# ethernet.net
KiCad netlist of a schematic drawn in Altium Designer
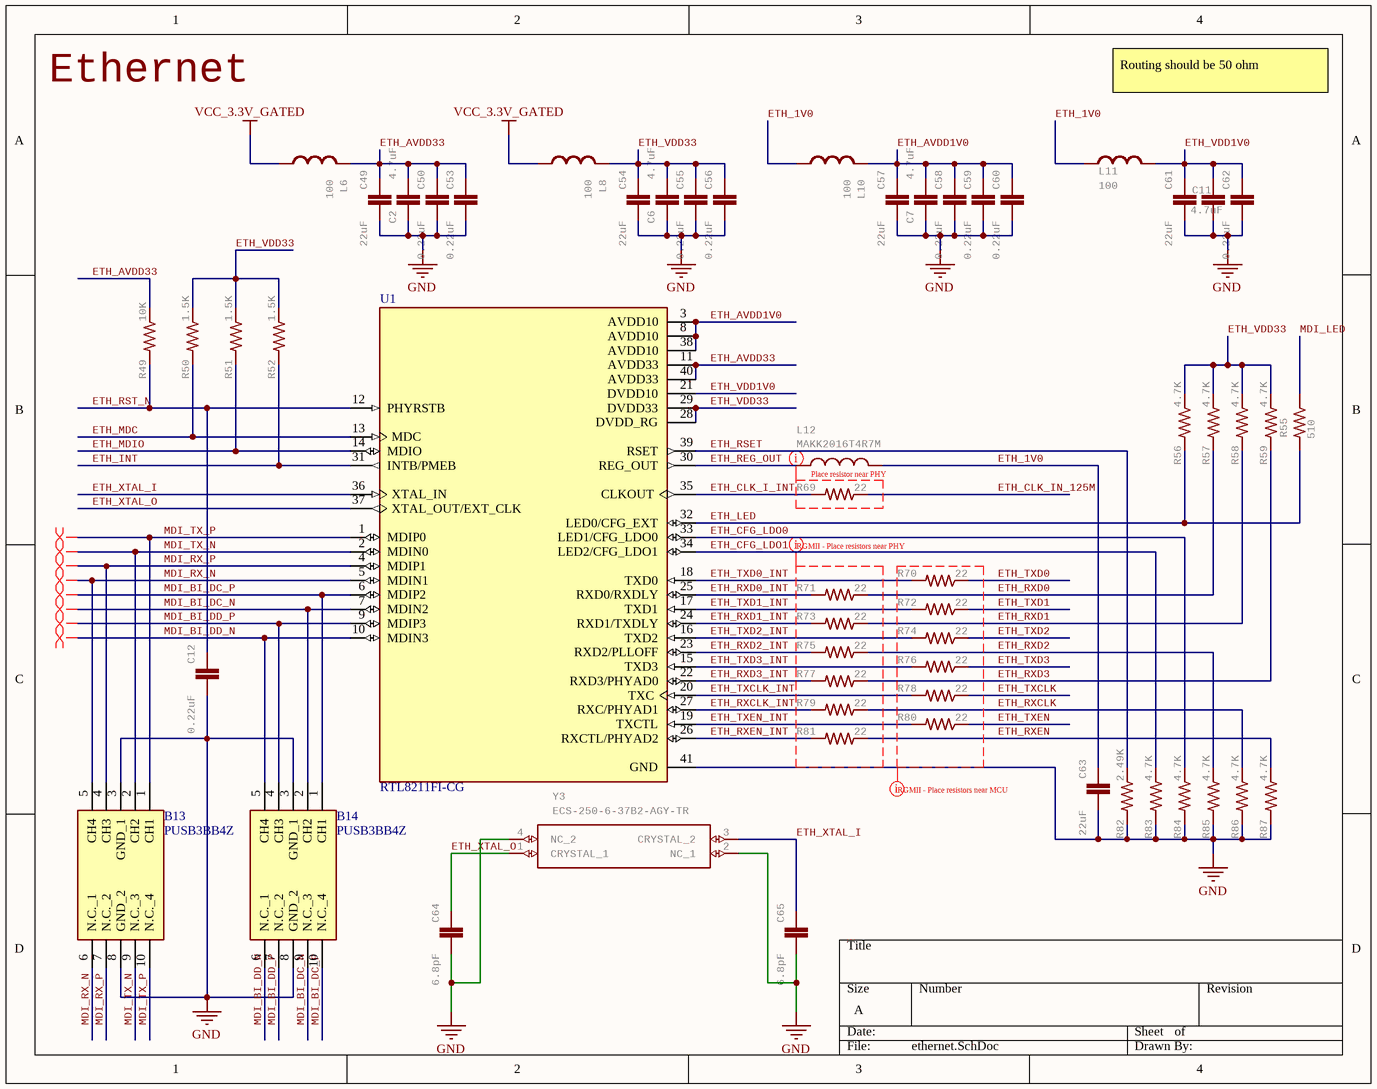
[diagram p0: ethernet.SchDoc]

(export (version "E")
  (design (tool "Eeschema 10.0.6"))
  (components
    (comp (ref "B13")
      (value "PUSB3BB4Z")
      (footprint "SON50P100X250X50-10N")
      (description "PUSB3BB4 - Extremely low capacitance bidirectional ESD protection diode array@en-us")
      (fields (field (name "MOUSER PART NUMBER") "771-PUSB3BB4Z"))
      (libsource (lib "PUSB3BB4Z") (part "PUSB3BB4Z"))
    )
    (comp (ref "B14")
      (value "PUSB3BB4Z")
      (footprint "SON50P100X250X50-10N")
      (description "PUSB3BB4 - Extremely low capacitance bidirectional ESD protection diode array@en-us")
      (fields (field (name "MOUSER PART NUMBER") "771-PUSB3BB4Z"))
      (libsource (lib "PUSB3BB4Z") (part "PUSB3BB4Z"))
    )
    (comp (ref "C2")
      (value "4.7uF")
      (footprint "0402-CAP")
      (description "CapacitorStandard 0603 ceramic capacitor, and 0.1\" leaded capacitor.")
      (fields (field (name "MPN") "JMK105BBJ475MV-F"))
      (libsource (lib "rt10") (part "CAP0402-CAP"))
    )
    (comp (ref "C6")
      (value "4.7uF")
      (footprint "0402-CAP")
      (description "CapacitorStandard 0603 ceramic capacitor, and 0.1\" leaded capacitor.")
      (fields (field (name "MPN") "JMK105BBJ475MV-F"))
      (libsource (lib "rt10") (part "CAP0402-CAP"))
    )
    (comp (ref "C7")
      (value "4.7uF")
      (footprint "0402-CAP")
      (description "CapacitorStandard 0603 ceramic capacitor, and 0.1\" leaded capacitor.")
      (fields (field (name "MPN") "JMK105BBJ475MV-F"))
      (libsource (lib "rt10") (part "CAP0402-CAP"))
    )
    (comp (ref "C11")
      (value "4.7uF")
      (footprint "0402-CAP")
      (description "CapacitorStandard 0603 ceramic capacitor, and 0.1\" leaded capacitor.")
      (fields (field (name "MPN") "JMK105BBJ475MV-F"))
      (libsource (lib "rt10") (part "CAP0402-CAP"))
    )
    (comp (ref "C12")
      (value "0.22uF")
      (footprint "C0201")
      (description "CAPACITOR, European symbol")
      (fields (field (name "MPN") "GRM033R60J224ME15D"))
      (libsource (lib "rt10") (part "C-EUC0201"))
    )
    (comp (ref "C49")
      (value "22uF")
      (footprint "0603-CAP")
      (fields (field (name "MPN") "GRM188R60G226MEA0D"))
      (libsource (lib "rt10") (part "22UF-0805-6.3V-20%"))
    )
    (comp (ref "C50")
      (value "0.22uF")
      (footprint "C0201")
      (description "CAPACITOR, European symbol")
      (fields (field (name "MPN") "GRM033R60J224ME15D"))
      (libsource (lib "rt10") (part "C-EUC0201"))
    )
    (comp (ref "C53")
      (value "0.22uF")
      (footprint "C0201")
      (description "CAPACITOR, European symbol")
      (fields (field (name "MPN") "GRM033R60J224ME15D"))
      (libsource (lib "rt10") (part "C-EUC0201"))
    )
    (comp (ref "C54")
      (value "22uF")
      (footprint "0603-CAP")
      (fields (field (name "MPN") "GRM188R60G226MEA0D"))
      (libsource (lib "rt10") (part "22UF-0805-6.3V-20%"))
    )
    (comp (ref "C55")
      (value "0.22uF")
      (footprint "C0201")
      (description "CAPACITOR, European symbol")
      (fields (field (name "MPN") "GRM033R60J224ME15D"))
      (libsource (lib "rt10") (part "C-EUC0201"))
    )
    (comp (ref "C56")
      (value "0.22uF")
      (footprint "C0201")
      (description "CAPACITOR, European symbol")
      (fields (field (name "MPN") "GRM033R60J224ME15D"))
      (libsource (lib "rt10") (part "C-EUC0201"))
    )
    (comp (ref "C57")
      (value "22uF")
      (footprint "0603-CAP")
      (fields (field (name "MPN") "GRM188R60G226MEA0D"))
      (libsource (lib "rt10") (part "22UF-0805-6.3V-20%"))
    )
    (comp (ref "C58")
      (value "0.22uF")
      (footprint "C0201")
      (description "CAPACITOR, European symbol")
      (fields (field (name "MPN") "GRM033R60J224ME15D"))
      (libsource (lib "rt10") (part "C-EUC0201"))
    )
    (comp (ref "C59")
      (value "0.22uF")
      (footprint "C0201")
      (description "CAPACITOR, European symbol")
      (fields (field (name "MPN") "GRM033R60J224ME15D"))
      (libsource (lib "rt10") (part "C-EUC0201"))
    )
    (comp (ref "C60")
      (value "0.22uF")
      (footprint "C0201")
      (description "CAPACITOR, European symbol")
      (fields (field (name "MPN") "GRM033R60J224ME15D"))
      (libsource (lib "rt10") (part "C-EUC0201"))
    )
    (comp (ref "C61")
      (value "22uF")
      (footprint "0603-CAP")
      (fields (field (name "MPN") "GRM188R60G226MEA0D"))
      (libsource (lib "rt10") (part "22UF-0805-6.3V-20%"))
    )
    (comp (ref "C62")
      (value "0.22uF")
      (footprint "C0201")
      (description "CAPACITOR, European symbol")
      (fields (field (name "MPN") "GRM033R60J224ME15D"))
      (libsource (lib "rt10") (part "C-EUC0201"))
    )
    (comp (ref "C63")
      (value "22uF")
      (footprint "0603-CAP")
      (fields (field (name "MPN") "GRM188R60G226MEA0D"))
      (libsource (lib "rt10") (part "22UF-0805-6.3V-20%"))
    )
    (comp (ref "C64")
      (value "6.8pF")
      (footprint "C0201")
      (description "CAPACITOR, European symbol")
      (fields (field (name "MPN") "GRM0335C1H6R8BA01D"))
      (libsource (lib "rt10") (part "C-EUC0201"))
    )
    (comp (ref "C65")
      (value "6.8pF")
      (footprint "C0201")
      (description "CAPACITOR, European symbol")
      (fields (field (name "MPN") "GRM0335C1H6R8BA01D"))
      (libsource (lib "rt10") (part "C-EUC0201"))
    )
    (comp (ref "L6")
      (value "100")
      (footprint "C0402")
      (fields (field (name "MPN") "MFBM1V1005-101-R"))
      (libsource (lib "rt10") (part "INDUCTOR0402"))
    )
    (comp (ref "L8")
      (value "100")
      (footprint "C0402")
      (fields (field (name "MPN") "MFBM1V1005-101-R"))
      (libsource (lib "rt10") (part "INDUCTOR0402"))
    )
    (comp (ref "L10")
      (value "100")
      (footprint "C0402")
      (fields (field (name "MPN") "MFBM1V1005-101-R"))
      (libsource (lib "rt10") (part "INDUCTOR0402"))
    )
    (comp (ref "L11")
      (value "100")
      (footprint "C0402")
      (fields (field (name "MPN") "MFBM1V1005-101-R"))
      (libsource (lib "rt10") (part "INDUCTOR0402"))
    )
    (comp (ref "L12")
      (value "MAKK2016T4R7M")
      (footprint "INDC2016X100N")
      (description "INDUCTOR, METAL CORE Check availability")
      (fields (field (name "MF") "Taiyo Yuden"))
      (libsource (lib "rt10") (part "MAKK2016T2R2M"))
    )
    (comp (ref "R49")
      (value "10K")
      (footprint "R0201")
      (fields (field (name "MPN") "CR0201-JW-103GLF"))
      (libsource (lib "openmv-ae3") (part "RESISTOR0402-RES"))
    )
    (comp (ref "R50")
      (value "1.5K")
      (footprint "R0201")
      (fields (field (name "MPN") "AC0201JR-071K5L"))
      (libsource (lib "openmv-ae3") (part "RESISTOR0402-RES"))
    )
    (comp (ref "R51")
      (value "1.5K")
      (footprint "R0201")
      (fields (field (name "MPN") "AC0201JR-071K5L"))
      (libsource (lib "openmv-ae3") (part "RESISTOR0402-RES"))
    )
    (comp (ref "R52")
      (value "1.5K")
      (footprint "R0201")
      (fields (field (name "MPN") "AC0201JR-071K5L"))
      (libsource (lib "openmv-ae3") (part "RESISTOR0402-RES"))
    )
    (comp (ref "R55")
      (value "510")
      (footprint "0402-RES")
      (description "ResistorBasic schematic elements and footprints for 0603, 1206, and PTH resistors.")
      (fields (field (name "MPN") "RC0402FR-07510RL"))
      (libsource (lib "rt10") (part "RESISTOR0402-RES"))
    )
    (comp (ref "R56")
      (value "4.7K")
      (footprint "R0201")
      (fields (field (name "MPN") "CR0201-FW-4701GLF"))
      (libsource (lib "openmv-ae3") (part "RESISTOR0402-RES"))
    )
    (comp (ref "R57")
      (value "4.7K")
      (footprint "R0201")
      (fields (field (name "MPN") "CR0201-FW-4701GLF"))
      (libsource (lib "openmv-ae3") (part "RESISTOR0402-RES"))
    )
    (comp (ref "R58")
      (value "4.7K")
      (footprint "R0201")
      (fields (field (name "MPN") "CR0201-FW-4701GLF"))
      (libsource (lib "openmv-ae3") (part "RESISTOR0402-RES"))
    )
    (comp (ref "R59")
      (value "4.7K")
      (footprint "R0201")
      (fields (field (name "MPN") "CR0201-FW-4701GLF"))
      (libsource (lib "openmv-ae3") (part "RESISTOR0402-RES"))
    )
    (comp (ref "R69")
      (value "22")
      (footprint "R0201")
      (fields (field (name "MPN") "CR0201-JW-220GLF"))
      (libsource (lib "openmv-ae3") (part "RESISTOR0402-RES"))
    )
    (comp (ref "R70")
      (value "22")
      (footprint "R0201")
      (fields (field (name "MPN") "CR0201-JW-220GLF"))
      (libsource (lib "openmv-ae3") (part "RESISTOR0402-RES"))
    )
    (comp (ref "R71")
      (value "22")
      (footprint "R0201")
      (fields (field (name "MPN") "CR0201-JW-220GLF"))
      (libsource (lib "openmv-ae3") (part "RESISTOR0402-RES"))
    )
    (comp (ref "R72")
      (value "22")
      (footprint "R0201")
      (fields (field (name "MPN") "CR0201-JW-220GLF"))
      (libsource (lib "openmv-ae3") (part "RESISTOR0402-RES"))
    )
    (comp (ref "R73")
      (value "22")
      (footprint "R0201")
      (fields (field (name "MPN") "CR0201-JW-220GLF"))
      (libsource (lib "openmv-ae3") (part "RESISTOR0402-RES"))
    )
    (comp (ref "R74")
      (value "22")
      (footprint "R0201")
      (fields (field (name "MPN") "CR0201-JW-220GLF"))
      (libsource (lib "openmv-ae3") (part "RESISTOR0402-RES"))
    )
    (comp (ref "R75")
      (value "22")
      (footprint "R0201")
      (fields (field (name "MPN") "CR0201-JW-220GLF"))
      (libsource (lib "openmv-ae3") (part "RESISTOR0402-RES"))
    )
    (comp (ref "R76")
      (value "22")
      (footprint "R0201")
      (fields (field (name "MPN") "CR0201-JW-220GLF"))
      (libsource (lib "openmv-ae3") (part "RESISTOR0402-RES"))
    )
    (comp (ref "R77")
      (value "22")
      (footprint "R0201")
      (fields (field (name "MPN") "CR0201-JW-220GLF"))
      (libsource (lib "openmv-ae3") (part "RESISTOR0402-RES"))
    )
    (comp (ref "R78")
      (value "22")
      (footprint "R0201")
      (fields (field (name "MPN") "CR0201-JW-220GLF"))
      (libsource (lib "openmv-ae3") (part "RESISTOR0402-RES"))
    )
    (comp (ref "R79")
      (value "22")
      (footprint "R0201")
      (fields (field (name "MPN") "CR0201-JW-220GLF"))
      (libsource (lib "openmv-ae3") (part "RESISTOR0402-RES"))
    )
    (comp (ref "R80")
      (value "22")
      (footprint "R0201")
      (fields (field (name "MPN") "CR0201-JW-220GLF"))
      (libsource (lib "openmv-ae3") (part "RESISTOR0402-RES"))
    )
    (comp (ref "R81")
      (value "22")
      (footprint "R0201")
      (fields (field (name "MPN") "CR0201-JW-220GLF"))
      (libsource (lib "openmv-ae3") (part "RESISTOR0402-RES"))
    )
    (comp (ref "R82")
      (value "2.49K")
      (footprint "R0201")
      (fields (field (name "MPN") "RC0201FR-072K49L"))
      (libsource (lib "openmv-ae3") (part "RESISTOR0402-RES"))
    )
    (comp (ref "R83")
      (value "4.7K")
      (footprint "R0201")
      (fields (field (name "MPN") "CR0201-FW-4701GLF"))
      (libsource (lib "openmv-ae3") (part "RESISTOR0402-RES"))
    )
    (comp (ref "R84")
      (value "4.7K")
      (footprint "R0201")
      (fields (field (name "MPN") "CR0201-FW-4701GLF"))
      (libsource (lib "openmv-ae3") (part "RESISTOR0402-RES"))
    )
    (comp (ref "R85")
      (value "4.7K")
      (footprint "R0201")
      (fields (field (name "MPN") "CR0201-FW-4701GLF"))
      (libsource (lib "openmv-ae3") (part "RESISTOR0402-RES"))
    )
    (comp (ref "R86")
      (value "4.7K")
      (footprint "R0201")
      (fields (field (name "MPN") "CR0201-FW-4701GLF"))
      (libsource (lib "openmv-ae3") (part "RESISTOR0402-RES"))
    )
    (comp (ref "R87")
      (value "4.7K")
      (footprint "R0201")
      (fields (field (name "MPN") "CR0201-FW-4701GLF"))
      (libsource (lib "openmv-ae3") (part "RESISTOR0402-RES"))
    )
    (comp (ref "U1")
      (value "RTL8211FI-CG")
      (footprint "RTL8211FI-CG")
      (description "GbE PHY with RGMIII interface & EEE feature (Switch Regulator), QFN40")
      (fields (field (name "MF") "Realtek Semiconductor Corp") (field (name "MP") "RTL8211F-CG"))
      (libsource (lib "stm32n657") (part "RTL8211F-CG"))
    )
    (comp (ref "Y3")
      (value "ECS-250-6-37B2-AGY-TR")
      (footprint "XRCGB24M000F3M00R0")
      (description "Murata 48MHz Crystal +/-30ppm SMD 4-Pin 2 x 1.6 x 0.7mm   Source:  Datasheet")
      (fields
        (field (name "MANUFACTURER_PART_NUMBER") "XRCGB48M000F0L00R0")
        (field (name "MOUSER_PART_NUMBER") "81-XRCGB48M000F0L00R0")
      )
      (libsource (lib "rt10") (part "XRCGB24M000F3M00R0"))
    )
  )
  (nets
    (net (code "1") (name "/ETH_1V0") (class "Default")
      (node (ref "C63") (pin "1") (pinfunction "1_1") (pintype "passive"))
      (node (ref "L10") (pin "1") (pinfunction "1_1") (pintype "passive"))
      (node (ref "L11") (pin "1") (pinfunction "1_1") (pintype "passive"))
      (node (ref "L12") (pin "2") (pinfunction "2_2") (pintype "passive"))
    )
    (net (code "2") (name "/ETH_AVDD1V0") (class "Default")
      (node (ref "C57") (pin "1") (pinfunction "1_1") (pintype "passive"))
      (node (ref "C58") (pin "1") (pinfunction "1_1") (pintype "passive"))
      (node (ref "C59") (pin "1") (pinfunction "1_1") (pintype "passive"))
      (node (ref "C60") (pin "1") (pinfunction "1_1") (pintype "passive"))
      (node (ref "C7") (pin "2") (pinfunction "2_2") (pintype "passive"))
      (node (ref "L10") (pin "2") (pinfunction "2_2") (pintype "passive"))
      (node (ref "U1") (pin "3") (pinfunction "AVDD10_3") (pintype "power_in"))
      (node (ref "U1") (pin "38") (pinfunction "AVDD10_38") (pintype "power_in"))
      (node (ref "U1") (pin "8") (pinfunction "AVDD10_8") (pintype "power_in"))
    )
    (net (code "3") (name "/ETH_AVDD33") (class "Default")
      (node (ref "C2") (pin "2") (pinfunction "2_2") (pintype "passive"))
      (node (ref "C49") (pin "1") (pinfunction "1_1") (pintype "passive"))
      (node (ref "C50") (pin "1") (pinfunction "1_1") (pintype "passive"))
      (node (ref "C53") (pin "1") (pinfunction "1_1") (pintype "passive"))
      (node (ref "L6") (pin "2") (pinfunction "2_2") (pintype "passive"))
      (node (ref "R49") (pin "1") (pinfunction "1_1") (pintype "passive"))
      (node (ref "U1") (pin "11") (pinfunction "AVDD33_11") (pintype "power_in"))
      (node (ref "U1") (pin "40") (pinfunction "AVDD33_40") (pintype "power_in"))
    )
    (net (code "4") (name "/ETH_CFG_LDO0") (class "Default")
      (node (ref "R84") (pin "1") (pinfunction "1_1") (pintype "passive"))
      (node (ref "U1") (pin "33") (pinfunction "LED1/CFG_LDO0_33") (pintype "bidirectional"))
    )
    (net (code "5") (name "/ETH_CFG_LDO1") (class "Default")
      (node (ref "R83") (pin "1") (pinfunction "1_1") (pintype "passive"))
      (node (ref "U1") (pin "34") (pinfunction "LED2/CFG_LDO1_34") (pintype "bidirectional"))
    )
    (net (code "6") (name "/ETH_CLK_IN_125M") (class "Default")
      (node (ref "R69") (pin "1") (pinfunction "1_1") (pintype "passive"))
    )
    (net (code "7") (name "/ETH_CLK_I_INT") (class "Default")
      (node (ref "R69") (pin "2") (pinfunction "2_2") (pintype "passive"))
      (node (ref "U1") (pin "35") (pinfunction "CLKOUT_35") (pintype "output"))
    )
    (net (code "8") (name "/ETH_INT") (class "Default")
      (node (ref "R52") (pin "2") (pinfunction "2_2") (pintype "passive"))
      (node (ref "U1") (pin "31") (pinfunction "INTB/PMEB_31") (pintype "output"))
    )
    (net (code "9") (name "/ETH_LED") (class "Default")
      (node (ref "R55") (pin "2") (pinfunction "2_2") (pintype "passive"))
      (node (ref "R56") (pin "2") (pinfunction "2_2") (pintype "passive"))
      (node (ref "U1") (pin "32") (pinfunction "LED0/CFG_EXT_32") (pintype "bidirectional"))
    )
    (net (code "10") (name "/ETH_MDC") (class "Default")
      (node (ref "R50") (pin "2") (pinfunction "2_2") (pintype "passive"))
      (node (ref "U1") (pin "13") (pinfunction "MDC_13") (pintype "input"))
    )
    (net (code "11") (name "/ETH_MDIO") (class "Default")
      (node (ref "R51") (pin "2") (pinfunction "2_2") (pintype "passive"))
      (node (ref "U1") (pin "14") (pinfunction "MDIO_14") (pintype "bidirectional"))
    )
    (net (code "12") (name "/ETH_REG_OUT") (class "Default")
      (node (ref "L12") (pin "1") (pinfunction "1_1") (pintype "passive"))
      (node (ref "U1") (pin "30") (pinfunction "REG_OUT_30") (pintype "output"))
    )
    (net (code "13") (name "/ETH_RSET") (class "Default")
      (node (ref "R82") (pin "1") (pinfunction "1_1") (pintype "passive"))
      (node (ref "U1") (pin "39") (pinfunction "RSET_39") (pintype "output"))
    )
    (net (code "14") (name "/ETH_RST_N") (class "Default")
      (node (ref "C12") (pin "1") (pinfunction "1_1") (pintype "passive"))
      (node (ref "R49") (pin "2") (pinfunction "2_2") (pintype "passive"))
      (node (ref "U1") (pin "12") (pinfunction "PHYRSTB_12") (pintype "input"))
    )
    (net (code "15") (name "/ETH_RXCLK") (class "Default")
      (node (ref "R79") (pin "1") (pinfunction "1_1") (pintype "passive"))
      (node (ref "R86") (pin "1") (pinfunction "1_1") (pintype "passive"))
    )
    (net (code "16") (name "/ETH_RXCLK_INT") (class "Default")
      (node (ref "R79") (pin "2") (pinfunction "2_2") (pintype "passive"))
      (node (ref "U1") (pin "27") (pinfunction "RXC/PHYAD1_27") (pintype "bidirectional"))
    )
    (net (code "17") (name "/ETH_RXD0") (class "Default")
      (node (ref "R57") (pin "2") (pinfunction "2_2") (pintype "passive"))
      (node (ref "R71") (pin "1") (pinfunction "1_1") (pintype "passive"))
    )
    (net (code "18") (name "/ETH_RXD0_INT") (class "Default")
      (node (ref "R71") (pin "2") (pinfunction "2_2") (pintype "passive"))
      (node (ref "U1") (pin "25") (pinfunction "RXD0/RXDLY_25") (pintype "bidirectional"))
    )
    (net (code "19") (name "/ETH_RXD1") (class "Default")
      (node (ref "R58") (pin "2") (pinfunction "2_2") (pintype "passive"))
      (node (ref "R73") (pin "1") (pinfunction "1_1") (pintype "passive"))
    )
    (net (code "20") (name "/ETH_RXD1_INT") (class "Default")
      (node (ref "R73") (pin "2") (pinfunction "2_2") (pintype "passive"))
      (node (ref "U1") (pin "24") (pinfunction "RXD1/TXDLY_24") (pintype "bidirectional"))
    )
    (net (code "21") (name "/ETH_RXD2") (class "Default")
      (node (ref "R75") (pin "1") (pinfunction "1_1") (pintype "passive"))
      (node (ref "R85") (pin "1") (pinfunction "1_1") (pintype "passive"))
    )
    (net (code "22") (name "/ETH_RXD2_INT") (class "Default")
      (node (ref "R75") (pin "2") (pinfunction "2_2") (pintype "passive"))
      (node (ref "U1") (pin "23") (pinfunction "RXD2/PLLOFF_23") (pintype "bidirectional"))
    )
    (net (code "23") (name "/ETH_RXD3") (class "Default")
      (node (ref "R59") (pin "2") (pinfunction "2_2") (pintype "passive"))
      (node (ref "R77") (pin "1") (pinfunction "1_1") (pintype "passive"))
    )
    (net (code "24") (name "/ETH_RXD3_INT") (class "Default")
      (node (ref "R77") (pin "2") (pinfunction "2_2") (pintype "passive"))
      (node (ref "U1") (pin "22") (pinfunction "RXD3/PHYAD0_22") (pintype "bidirectional"))
    )
    (net (code "25") (name "/ETH_RXEN") (class "Default")
      (node (ref "R81") (pin "1") (pinfunction "1_1") (pintype "passive"))
      (node (ref "R87") (pin "1") (pinfunction "1_1") (pintype "passive"))
    )
    (net (code "26") (name "/ETH_RXEN_INT") (class "Default")
      (node (ref "R81") (pin "2") (pinfunction "2_2") (pintype "passive"))
      (node (ref "U1") (pin "26") (pinfunction "RXCTL/PHYAD2_26") (pintype "bidirectional"))
    )
    (net (code "27") (name "/ETH_TXCLK") (class "Default")
      (node (ref "R78") (pin "1") (pinfunction "1_1") (pintype "passive"))
    )
    (net (code "28") (name "/ETH_TXCLK_INT") (class "Default")
      (node (ref "R78") (pin "2") (pinfunction "2_2") (pintype "passive"))
      (node (ref "U1") (pin "20") (pinfunction "TXC_20") (pintype "input"))
    )
    (net (code "29") (name "/ETH_TXD0") (class "Default")
      (node (ref "R70") (pin "1") (pinfunction "1_1") (pintype "passive"))
    )
    (net (code "30") (name "/ETH_TXD0_INT") (class "Default")
      (node (ref "R70") (pin "2") (pinfunction "2_2") (pintype "passive"))
      (node (ref "U1") (pin "18") (pinfunction "TXD0_18") (pintype "input"))
    )
    (net (code "31") (name "/ETH_TXD1") (class "Default")
      (node (ref "R72") (pin "1") (pinfunction "1_1") (pintype "passive"))
    )
    (net (code "32") (name "/ETH_TXD1_INT") (class "Default")
      (node (ref "R72") (pin "2") (pinfunction "2_2") (pintype "passive"))
      (node (ref "U1") (pin "17") (pinfunction "TXD1_17") (pintype "input"))
    )
    (net (code "33") (name "/ETH_TXD2") (class "Default")
      (node (ref "R74") (pin "1") (pinfunction "1_1") (pintype "passive"))
    )
    (net (code "34") (name "/ETH_TXD2_INT") (class "Default")
      (node (ref "R74") (pin "2") (pinfunction "2_2") (pintype "passive"))
      (node (ref "U1") (pin "16") (pinfunction "TXD2_16") (pintype "input"))
    )
    (net (code "35") (name "/ETH_TXD3") (class "Default")
      (node (ref "R76") (pin "1") (pinfunction "1_1") (pintype "passive"))
    )
    (net (code "36") (name "/ETH_TXD3_INT") (class "Default")
      (node (ref "R76") (pin "2") (pinfunction "2_2") (pintype "passive"))
      (node (ref "U1") (pin "15") (pinfunction "TXD3_15") (pintype "input"))
    )
    (net (code "37") (name "/ETH_TXEN") (class "Default")
      (node (ref "R80") (pin "1") (pinfunction "1_1") (pintype "passive"))
    )
    (net (code "38") (name "/ETH_TXEN_INT") (class "Default")
      (node (ref "R80") (pin "2") (pinfunction "2_2") (pintype "passive"))
      (node (ref "U1") (pin "19") (pinfunction "TXCTL_19") (pintype "input"))
    )
    (net (code "39") (name "/ETH_VDD1V0") (class "Default")
      (node (ref "C11") (pin "2") (pinfunction "2_2") (pintype "passive"))
      (node (ref "C61") (pin "1") (pinfunction "1_1") (pintype "passive"))
      (node (ref "C62") (pin "1") (pinfunction "1_1") (pintype "passive"))
      (node (ref "L11") (pin "2") (pinfunction "2_2") (pintype "passive"))
      (node (ref "U1") (pin "21") (pinfunction "DVDD10_21") (pintype "power_in"))
    )
    (net (code "40") (name "/ETH_VDD33") (class "Default")
      (node (ref "C54") (pin "1") (pinfunction "1_1") (pintype "passive"))
      (node (ref "C55") (pin "1") (pinfunction "1_1") (pintype "passive"))
      (node (ref "C56") (pin "1") (pinfunction "1_1") (pintype "passive"))
      (node (ref "C6") (pin "2") (pinfunction "2_2") (pintype "passive"))
      (node (ref "L8") (pin "2") (pinfunction "2_2") (pintype "passive"))
      (node (ref "R50") (pin "1") (pinfunction "1_1") (pintype "passive"))
      (node (ref "R51") (pin "1") (pinfunction "1_1") (pintype "passive"))
      (node (ref "R52") (pin "1") (pinfunction "1_1") (pintype "passive"))
      (node (ref "R56") (pin "1") (pinfunction "1_1") (pintype "passive"))
      (node (ref "R57") (pin "1") (pinfunction "1_1") (pintype "passive"))
      (node (ref "R58") (pin "1") (pinfunction "1_1") (pintype "passive"))
      (node (ref "R59") (pin "1") (pinfunction "1_1") (pintype "passive"))
      (node (ref "U1") (pin "28") (pinfunction "DVDD_RG_28") (pintype "power_in"))
      (node (ref "U1") (pin "29") (pinfunction "DVDD33_29") (pintype "power_in"))
    )
    (net (code "41") (name "/ETH_XTAL_I") (class "Default")
      (node (ref "C65") (pin "1") (pinfunction "1_1") (pintype "passive"))
      (node (ref "U1") (pin "36") (pinfunction "XTAL_IN_36") (pintype "input"))
      (node (ref "Y3") (pin "3") (pinfunction "CRYSTAL_2_3") (pintype "bidirectional"))
    )
    (net (code "42") (name "/ETH_XTAL_O") (class "Default")
      (node (ref "C64") (pin "1") (pinfunction "1_1") (pintype "passive"))
      (node (ref "U1") (pin "37") (pinfunction "XTAL_OUT/EXT_CLK_37") (pintype "output"))
      (node (ref "Y3") (pin "1") (pinfunction "CRYSTAL_1_1") (pintype "bidirectional"))
    )
    (net (code "43") (name "/MDI_BI_DC_N") (class "Default")
      (node (ref "B14") (pin "2") (pinfunction "CH2_2") (pintype "passive"))
      (node (ref "B14") (pin "9") (pinfunction "N.C._3_9") (pintype "passive"))
      (node (ref "U1") (pin "7") (pinfunction "MDIN2_7") (pintype "bidirectional"))
    )
    (net (code "44") (name "/MDI_BI_DC_P") (class "Default")
      (node (ref "B14") (pin "1") (pinfunction "CH1_1") (pintype "passive"))
      (node (ref "B14") (pin "10") (pinfunction "N.C._4_10") (pintype "passive"))
      (node (ref "U1") (pin "6") (pinfunction "MDIP2_6") (pintype "bidirectional"))
    )
    (net (code "45") (name "/MDI_BI_DD_N") (class "Default")
      (node (ref "B14") (pin "5") (pinfunction "CH4_5") (pintype "passive"))
      (node (ref "B14") (pin "6") (pinfunction "N.C._1_6") (pintype "passive"))
      (node (ref "U1") (pin "10") (pinfunction "MDIN3_10") (pintype "bidirectional"))
    )
    (net (code "46") (name "/MDI_BI_DD_P") (class "Default")
      (node (ref "B14") (pin "4") (pinfunction "CH3_4") (pintype "passive"))
      (node (ref "B14") (pin "7") (pinfunction "N.C._2_7") (pintype "passive"))
      (node (ref "U1") (pin "9") (pinfunction "MDIP3_9") (pintype "bidirectional"))
    )
    (net (code "47") (name "/MDI_LED") (class "Default")
      (node (ref "R55") (pin "1") (pinfunction "1_1") (pintype "passive"))
    )
    (net (code "48") (name "/MDI_RX_N") (class "Default")
      (node (ref "B13") (pin "5") (pinfunction "CH4_5") (pintype "passive"))
      (node (ref "B13") (pin "6") (pinfunction "N.C._1_6") (pintype "passive"))
      (node (ref "U1") (pin "5") (pinfunction "MDIN1_5") (pintype "bidirectional"))
    )
    (net (code "49") (name "/MDI_RX_P") (class "Default")
      (node (ref "B13") (pin "4") (pinfunction "CH3_4") (pintype "passive"))
      (node (ref "B13") (pin "7") (pinfunction "N.C._2_7") (pintype "passive"))
      (node (ref "U1") (pin "4") (pinfunction "MDIP1_4") (pintype "bidirectional"))
    )
    (net (code "50") (name "/MDI_TX_N") (class "Default")
      (node (ref "B13") (pin "2") (pinfunction "CH2_2") (pintype "passive"))
      (node (ref "B13") (pin "9") (pinfunction "N.C._3_9") (pintype "passive"))
      (node (ref "U1") (pin "2") (pinfunction "MDIN0_2") (pintype "bidirectional"))
    )
    (net (code "51") (name "/MDI_TX_P") (class "Default")
      (node (ref "B13") (pin "1") (pinfunction "CH1_1") (pintype "passive"))
      (node (ref "B13") (pin "10") (pinfunction "N.C._4_10") (pintype "passive"))
      (node (ref "U1") (pin "1") (pinfunction "MDIP0_1") (pintype "bidirectional"))
    )
    (net (code "52") (name "GND") (class "Default")
      (node (ref "B13") (pin "3") (pinfunction "GND_1_3") (pintype "passive"))
      (node (ref "B13") (pin "8") (pinfunction "GND_2_8") (pintype "passive"))
      (node (ref "B14") (pin "3") (pinfunction "GND_1_3") (pintype "passive"))
      (node (ref "B14") (pin "8") (pinfunction "GND_2_8") (pintype "passive"))
      (node (ref "C11") (pin "1") (pinfunction "1_1") (pintype "passive"))
      (node (ref "C12") (pin "2") (pinfunction "2_2") (pintype "passive"))
      (node (ref "C2") (pin "1") (pinfunction "1_1") (pintype "passive"))
      (node (ref "C49") (pin "2") (pinfunction "2_2") (pintype "passive"))
      (node (ref "C50") (pin "2") (pinfunction "2_2") (pintype "passive"))
      (node (ref "C53") (pin "2") (pinfunction "2_2") (pintype "passive"))
      (node (ref "C54") (pin "2") (pinfunction "2_2") (pintype "passive"))
      (node (ref "C55") (pin "2") (pinfunction "2_2") (pintype "passive"))
      (node (ref "C56") (pin "2") (pinfunction "2_2") (pintype "passive"))
      (node (ref "C57") (pin "2") (pinfunction "2_2") (pintype "passive"))
      (node (ref "C58") (pin "2") (pinfunction "2_2") (pintype "passive"))
      (node (ref "C59") (pin "2") (pinfunction "2_2") (pintype "passive"))
      (node (ref "C6") (pin "1") (pinfunction "1_1") (pintype "passive"))
      (node (ref "C60") (pin "2") (pinfunction "2_2") (pintype "passive"))
      (node (ref "C61") (pin "2") (pinfunction "2_2") (pintype "passive"))
      (node (ref "C62") (pin "2") (pinfunction "2_2") (pintype "passive"))
      (node (ref "C63") (pin "2") (pinfunction "2_2") (pintype "passive"))
      (node (ref "C64") (pin "2") (pinfunction "2_2") (pintype "passive"))
      (node (ref "C65") (pin "2") (pinfunction "2_2") (pintype "passive"))
      (node (ref "C7") (pin "1") (pinfunction "1_1") (pintype "passive"))
      (node (ref "R82") (pin "2") (pinfunction "2_2") (pintype "passive"))
      (node (ref "R83") (pin "2") (pinfunction "2_2") (pintype "passive"))
      (node (ref "R84") (pin "2") (pinfunction "2_2") (pintype "passive"))
      (node (ref "R85") (pin "2") (pinfunction "2_2") (pintype "passive"))
      (node (ref "R86") (pin "2") (pinfunction "2_2") (pintype "passive"))
      (node (ref "R87") (pin "2") (pinfunction "2_2") (pintype "passive"))
      (node (ref "U1") (pin "41") (pinfunction "GND_41") (pintype "power_in"))
      (node (ref "Y3") (pin "2") (pinfunction "NC_1_2") (pintype "bidirectional"))
      (node (ref "Y3") (pin "4") (pinfunction "NC_2_4") (pintype "bidirectional"))
    )
    (net (code "53") (name "VCC_3.3V_GATED") (class "Default")
      (node (ref "L6") (pin "1") (pinfunction "1_1") (pintype "passive"))
      (node (ref "L8") (pin "1") (pinfunction "1_1") (pintype "passive"))
    )
  )
)
